# PlytaGlowna.net
KiCad netlist of a schematic drawn in EAGLE
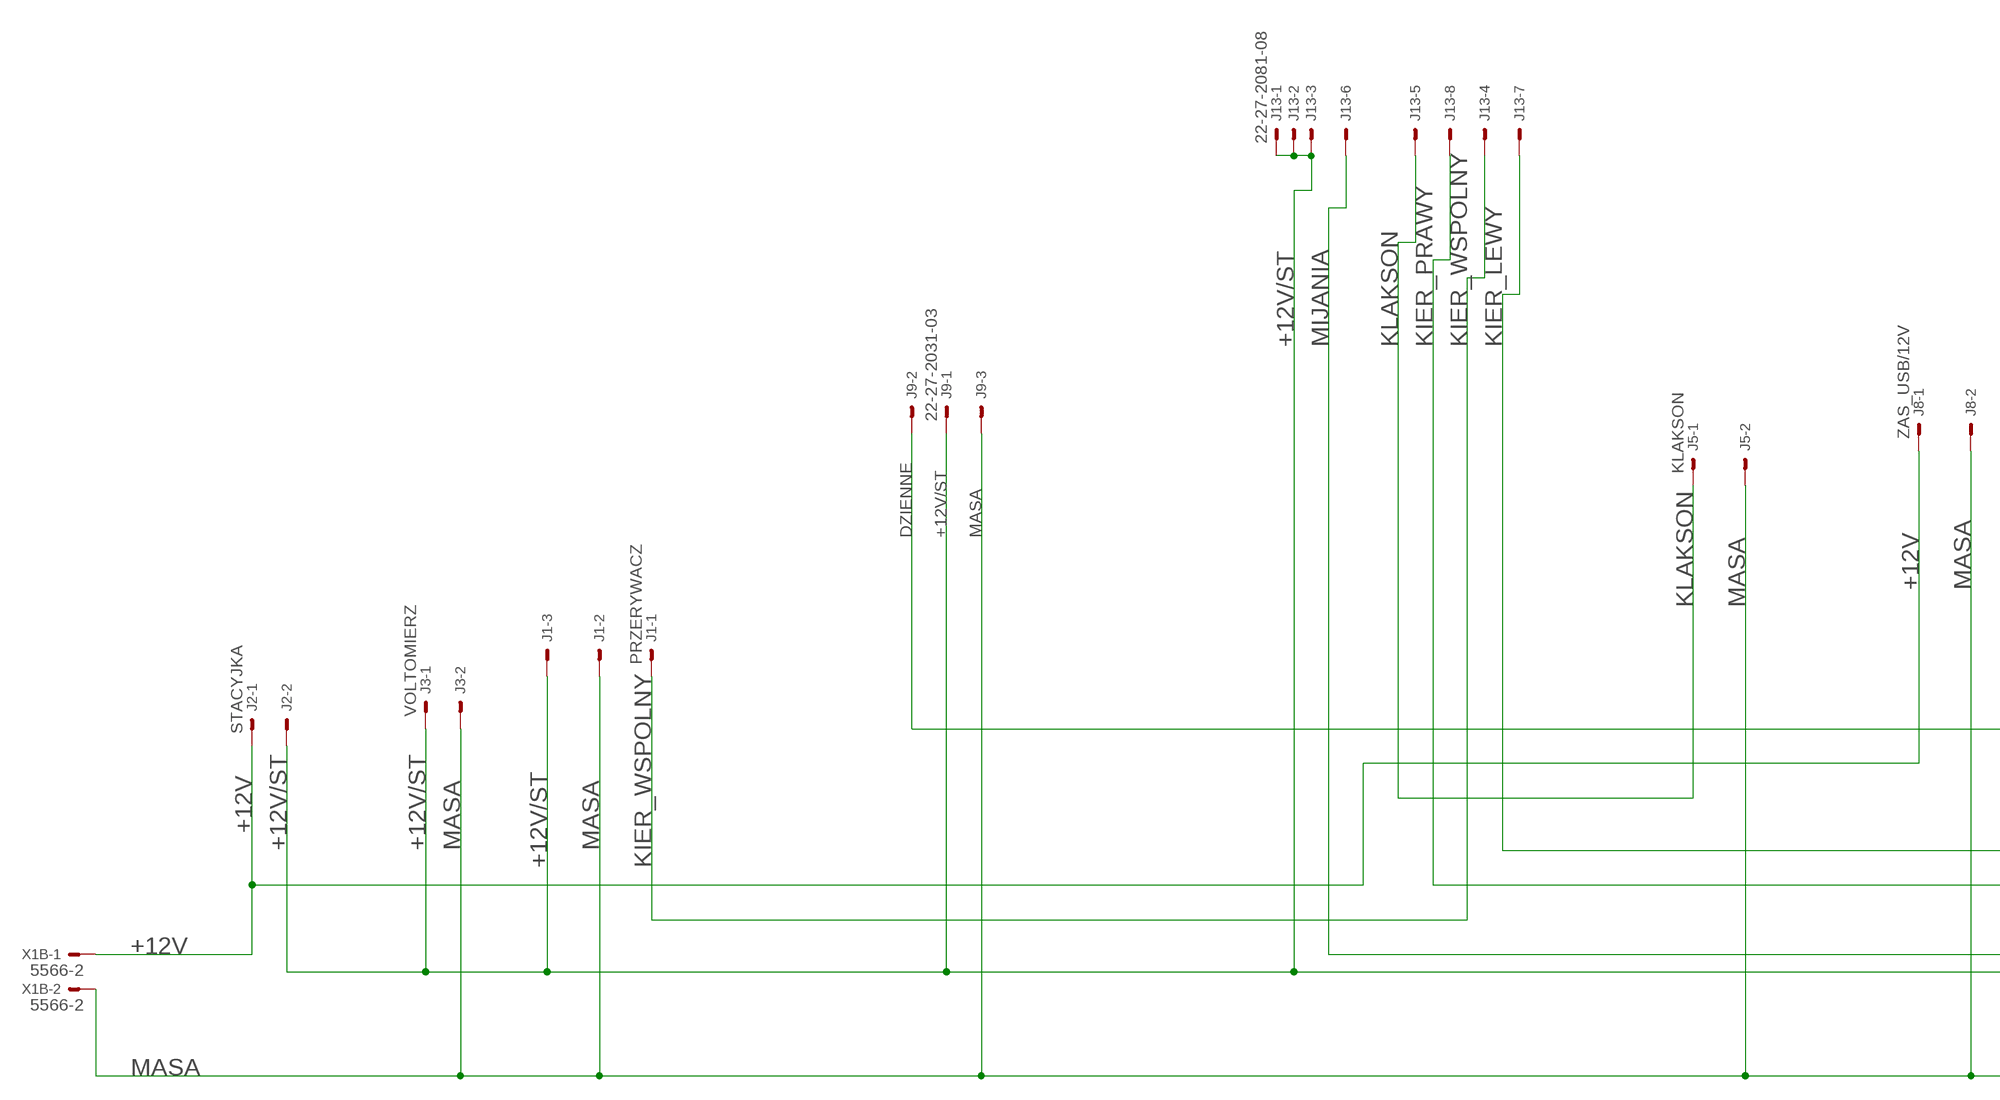
[diagram p0: schematic, sheet 1, part 1 of 2]
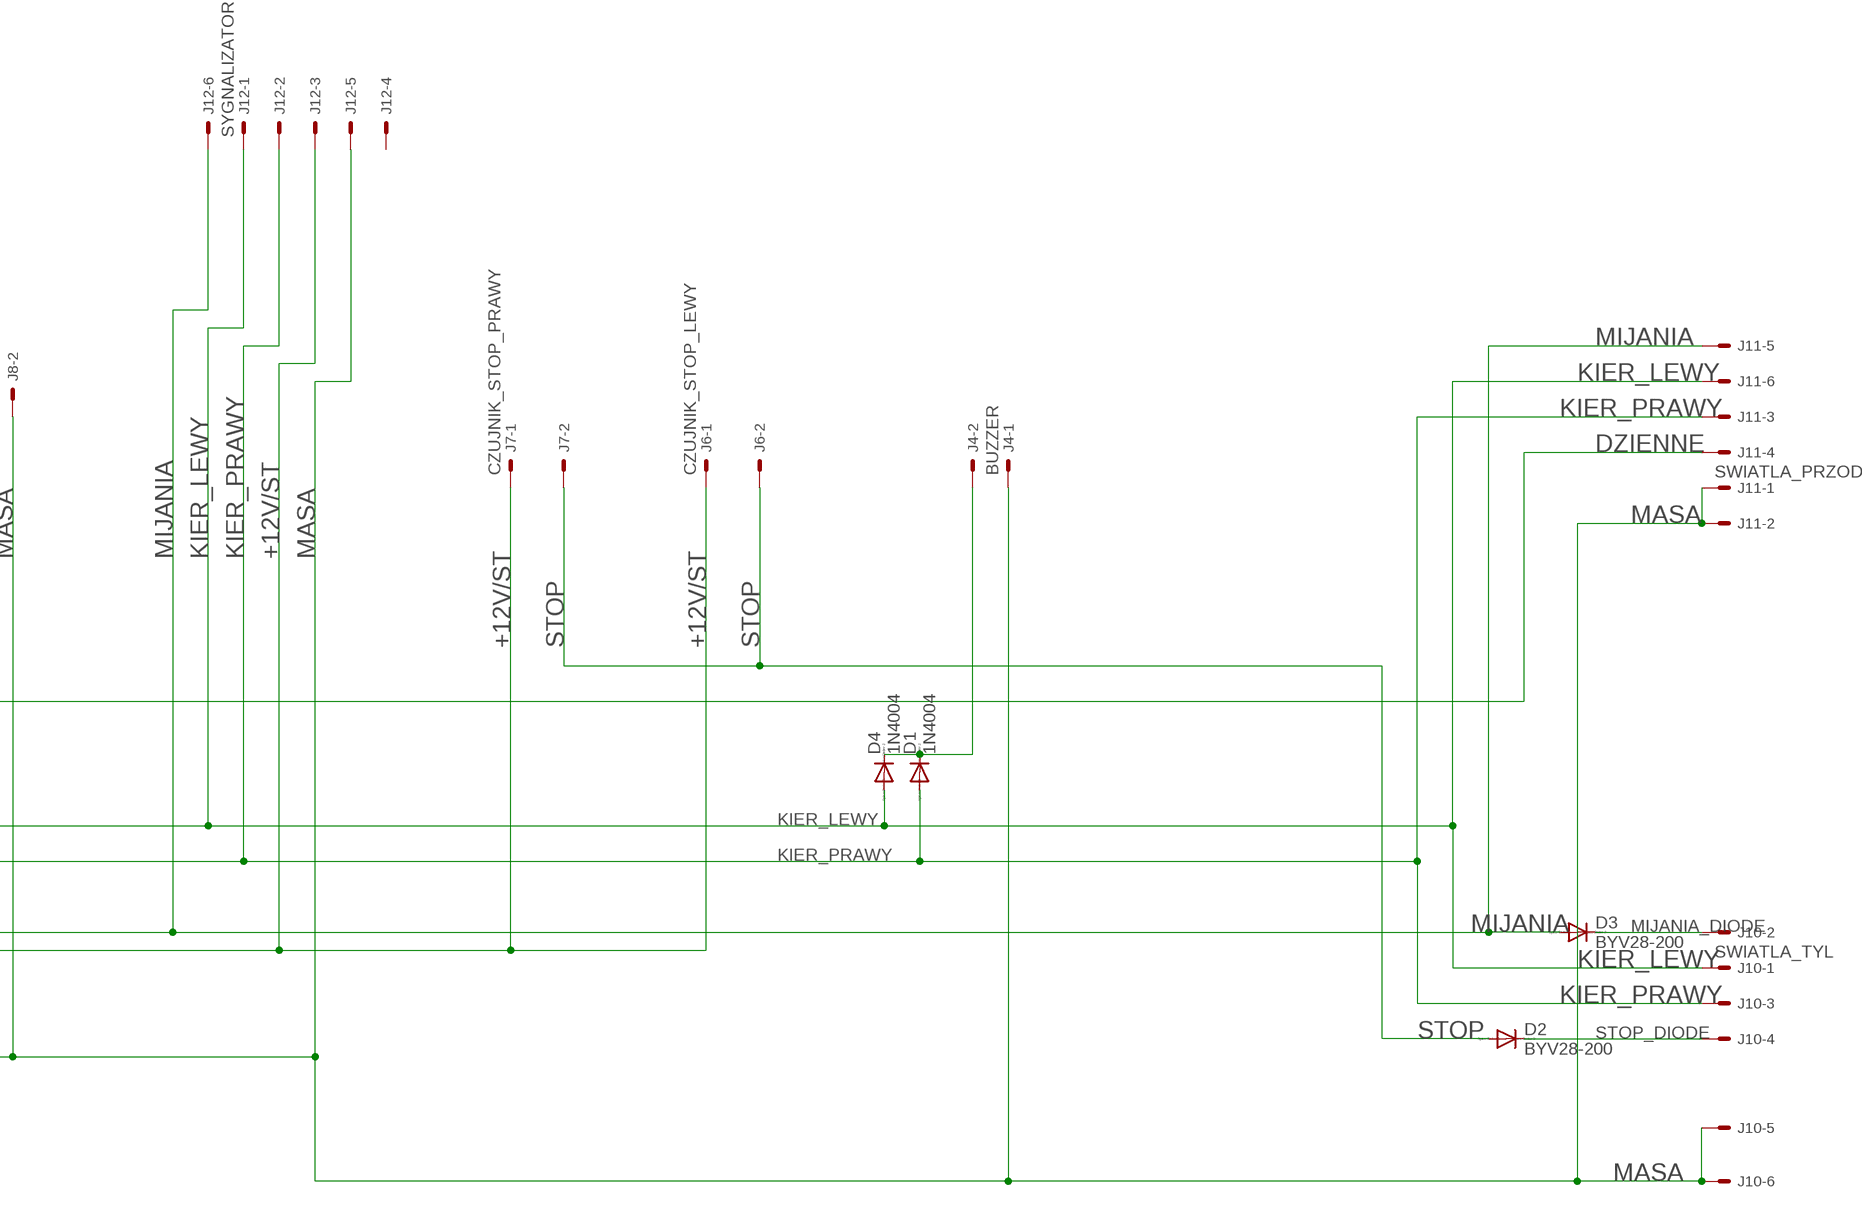
[diagram p1: schematic, sheet 1, part 2 of 2]

(export (version "E")
  (design (tool "Eeschema 10.0.6"))
  (components
    (comp (ref "D1")
      (value "1N4004")
      (footprint "eagle-import:DO41-10")
      (libsource (lib "eagle-import") (part "1N4004"))
    )
    (comp (ref "D2")
      (value "BYV28-200")
      (footprint "eagle-import:SOD64-10")
      (libsource (lib "eagle-import") (part "BYV28"))
    )
    (comp (ref "D3")
      (value "BYV28-200")
      (footprint "eagle-import:SOD64-10")
      (libsource (lib "eagle-import") (part "BYV28"))
    )
    (comp (ref "D4")
      (value "1N4004")
      (footprint "eagle-import:DO41-10")
      (libsource (lib "eagle-import") (part "1N4004"))
    )
    (comp (ref "J1")
      (value "PRZERYWACZ")
      (footprint "eagle-import:6410-03")
      (fields (field (name "MF") "MOLEX"))
      (libsource (lib "eagle-import") (part "22-?-0327-2031"))
    )
    (comp (ref "J2")
      (value "STACYJKA")
      (footprint "eagle-import:6410-02")
      (fields (field (name "MF") "MOLEX"))
      (libsource (lib "eagle-import") (part "22-?-0227-2021"))
    )
    (comp (ref "J3")
      (value "VOLTOMIERZ")
      (footprint "eagle-import:6410-02")
      (fields (field (name "MF") "MOLEX"))
      (libsource (lib "eagle-import") (part "22-?-0227-2021"))
    )
    (comp (ref "J4")
      (value "BUZZER")
      (footprint "eagle-import:6410-02")
      (fields (field (name "MF") "MOLEX"))
      (libsource (lib "eagle-import") (part "22-?-0227-2021"))
    )
    (comp (ref "J5")
      (value "KLAKSON")
      (footprint "eagle-import:6410-02")
      (fields (field (name "MF") "MOLEX"))
      (libsource (lib "eagle-import") (part "22-?-0227-2021"))
    )
    (comp (ref "J6")
      (value "CZUJNIK_STOP_LEWY")
      (footprint "eagle-import:6410-02")
      (fields (field (name "MF") "MOLEX"))
      (libsource (lib "eagle-import") (part "22-?-0227-2021"))
    )
    (comp (ref "J7")
      (value "CZUJNIK_STOP_PRAWY")
      (footprint "eagle-import:6410-02")
      (fields (field (name "MF") "MOLEX"))
      (libsource (lib "eagle-import") (part "22-?-0227-2021"))
    )
    (comp (ref "J8")
      (value "ZAS_USB/12V")
      (footprint "eagle-import:6410-02")
      (fields (field (name "MF") "MOLEX"))
      (libsource (lib "eagle-import") (part "22-?-0227-2021"))
    )
    (comp (ref "J9")
      (value "22-27-2031-03")
      (footprint "eagle-import:6410-03")
      (fields (field (name "MF") "MOLEX"))
      (libsource (lib "eagle-import") (part "22-?-0327-2031"))
    )
    (comp (ref "J10")
      (value "SWIATLA_TYL")
      (footprint "eagle-import:6410-06")
      (fields (field (name "MF") "MOLEX"))
      (libsource (lib "eagle-import") (part "22-?-0627-2061"))
    )
    (comp (ref "J11")
      (value "SWIATLA_PRZOD")
      (footprint "eagle-import:6410-06")
      (fields (field (name "MF") "MOLEX"))
      (libsource (lib "eagle-import") (part "22-?-0627-2061"))
    )
    (comp (ref "J12")
      (value "SYGNALIZATOR")
      (footprint "eagle-import:6410-06")
      (fields (field (name "MF") "MOLEX"))
      (libsource (lib "eagle-import") (part "22-?-0627-2061"))
    )
    (comp (ref "J13")
      (value "22-27-2081-08")
      (footprint "eagle-import:6410-08")
      (fields (field (name "MF") "MOLEX"))
      (libsource (lib "eagle-import") (part "22-?-0827-2081"))
    )
    (comp (ref "X1B")
      (value "5566-2")
      (footprint "eagle-import:5566-2")
      (libsource (lib "eagle-import") (part "5566-2"))
    )
  )
  (nets
    (net (code "1") (name "/+12V") (class "Default")
      (node (ref "J2") (pin "1") (pinfunction "S_1") (pintype "passive"))
      (node (ref "J8") (pin "1") (pinfunction "S_1") (pintype "passive"))
      (node (ref "X1B") (pin "1") (pinfunction "S_1") (pintype "passive"))
    )
    (net (code "2") (name "/+12V{slash}ST") (class "Default")
      (node (ref "J1") (pin "3") (pinfunction "S_3") (pintype "passive"))
      (node (ref "J12") (pin "3") (pinfunction "S_3") (pintype "passive"))
      (node (ref "J13") (pin "1") (pinfunction "S_1") (pintype "passive"))
      (node (ref "J13") (pin "2") (pinfunction "S_2") (pintype "passive"))
      (node (ref "J13") (pin "3") (pinfunction "S_3") (pintype "passive"))
      (node (ref "J2") (pin "2") (pinfunction "S_2") (pintype "passive"))
      (node (ref "J3") (pin "1") (pinfunction "S_1") (pintype "passive"))
      (node (ref "J6") (pin "1") (pinfunction "S_1") (pintype "passive"))
      (node (ref "J7") (pin "1") (pinfunction "S_1") (pintype "passive"))
      (node (ref "J9") (pin "1") (pinfunction "S_1") (pintype "passive"))
    )
    (net (code "3") (name "/DZIENNE") (class "Default")
      (node (ref "J11") (pin "4") (pinfunction "S_4") (pintype "passive"))
      (node (ref "J9") (pin "2") (pinfunction "S_2") (pintype "passive"))
    )
    (net (code "4") (name "/KIER_LEWY") (class "Default")
      (node (ref "D4") (pin "A") (pinfunction "A_A") (pintype "passive"))
      (node (ref "J10") (pin "1") (pinfunction "S_1") (pintype "passive"))
      (node (ref "J11") (pin "6") (pinfunction "S_6") (pintype "passive"))
      (node (ref "J12") (pin "1") (pinfunction "S_1") (pintype "passive"))
      (node (ref "J13") (pin "7") (pinfunction "S_7") (pintype "passive"))
    )
    (net (code "5") (name "/KIER_PRAWY") (class "Default")
      (node (ref "D1") (pin "A") (pinfunction "A_A") (pintype "passive"))
      (node (ref "J10") (pin "3") (pinfunction "S_3") (pintype "passive"))
      (node (ref "J11") (pin "3") (pinfunction "S_3") (pintype "passive"))
      (node (ref "J12") (pin "2") (pinfunction "S_2") (pintype "passive"))
      (node (ref "J13") (pin "8") (pinfunction "S_8") (pintype "passive"))
    )
    (net (code "6") (name "/KIER_WSPOLNY") (class "Default")
      (node (ref "J1") (pin "1") (pinfunction "S_1") (pintype "passive"))
      (node (ref "J13") (pin "4") (pinfunction "S_4") (pintype "passive"))
    )
    (net (code "7") (name "/KLAKSON") (class "Default")
      (node (ref "J13") (pin "5") (pinfunction "S_5") (pintype "passive"))
      (node (ref "J5") (pin "1") (pinfunction "S_1") (pintype "passive"))
    )
    (net (code "8") (name "/MASA") (class "Default")
      (node (ref "J1") (pin "2") (pinfunction "S_2") (pintype "passive"))
      (node (ref "J10") (pin "5") (pinfunction "S_5") (pintype "passive"))
      (node (ref "J10") (pin "6") (pinfunction "S_6") (pintype "passive"))
      (node (ref "J11") (pin "1") (pinfunction "S_1") (pintype "passive"))
      (node (ref "J11") (pin "2") (pinfunction "S_2") (pintype "passive"))
      (node (ref "J12") (pin "5") (pinfunction "S_5") (pintype "passive"))
      (node (ref "J3") (pin "2") (pinfunction "S_2") (pintype "passive"))
      (node (ref "J4") (pin "1") (pinfunction "S_1") (pintype "passive"))
      (node (ref "J5") (pin "2") (pinfunction "S_2") (pintype "passive"))
      (node (ref "J8") (pin "2") (pinfunction "S_2") (pintype "passive"))
      (node (ref "J9") (pin "3") (pinfunction "S_3") (pintype "passive"))
      (node (ref "X1B") (pin "2") (pinfunction "S_2") (pintype "passive"))
    )
    (net (code "9") (name "/MIJANIA") (class "Default")
      (node (ref "D3") (pin "A") (pinfunction "A_A") (pintype "passive"))
      (node (ref "J11") (pin "5") (pinfunction "S_5") (pintype "passive"))
      (node (ref "J12") (pin "6") (pinfunction "S_6") (pintype "passive"))
      (node (ref "J13") (pin "6") (pinfunction "S_6") (pintype "passive"))
    )
    (net (code "10") (name "/MIJANIA_DIODE") (class "Default")
      (node (ref "D3") (pin "C") (pinfunction "C_C") (pintype "passive"))
      (node (ref "J10") (pin "2") (pinfunction "S_2") (pintype "passive"))
    )
    (net (code "11") (name "/STOP") (class "Default")
      (node (ref "D2") (pin "A") (pinfunction "A_A") (pintype "passive"))
      (node (ref "J6") (pin "2") (pinfunction "S_2") (pintype "passive"))
      (node (ref "J7") (pin "2") (pinfunction "S_2") (pintype "passive"))
    )
    (net (code "12") (name "/STOP_DIODE") (class "Default")
      (node (ref "D2") (pin "C") (pinfunction "C_C") (pintype "passive"))
      (node (ref "J10") (pin "4") (pinfunction "S_4") (pintype "passive"))
    )
    (net (code "13") (name "Net-(J4B-S)") (class "Default")
      (node (ref "D1") (pin "C") (pinfunction "C_C") (pintype "passive"))
      (node (ref "D4") (pin "C") (pinfunction "C_C") (pintype "passive"))
      (node (ref "J4") (pin "2") (pinfunction "S_2") (pintype "passive"))
    )
    (net (code "14") (name "unconnected-(J12D-S-Pad4)") (class "Default")
      (node (ref "J12") (pin "4") (pinfunction "S_4") (pintype "passive"))
    )
  )
)
